# 2.net
KiCad netlist of a schematic drawn in Altium Designer
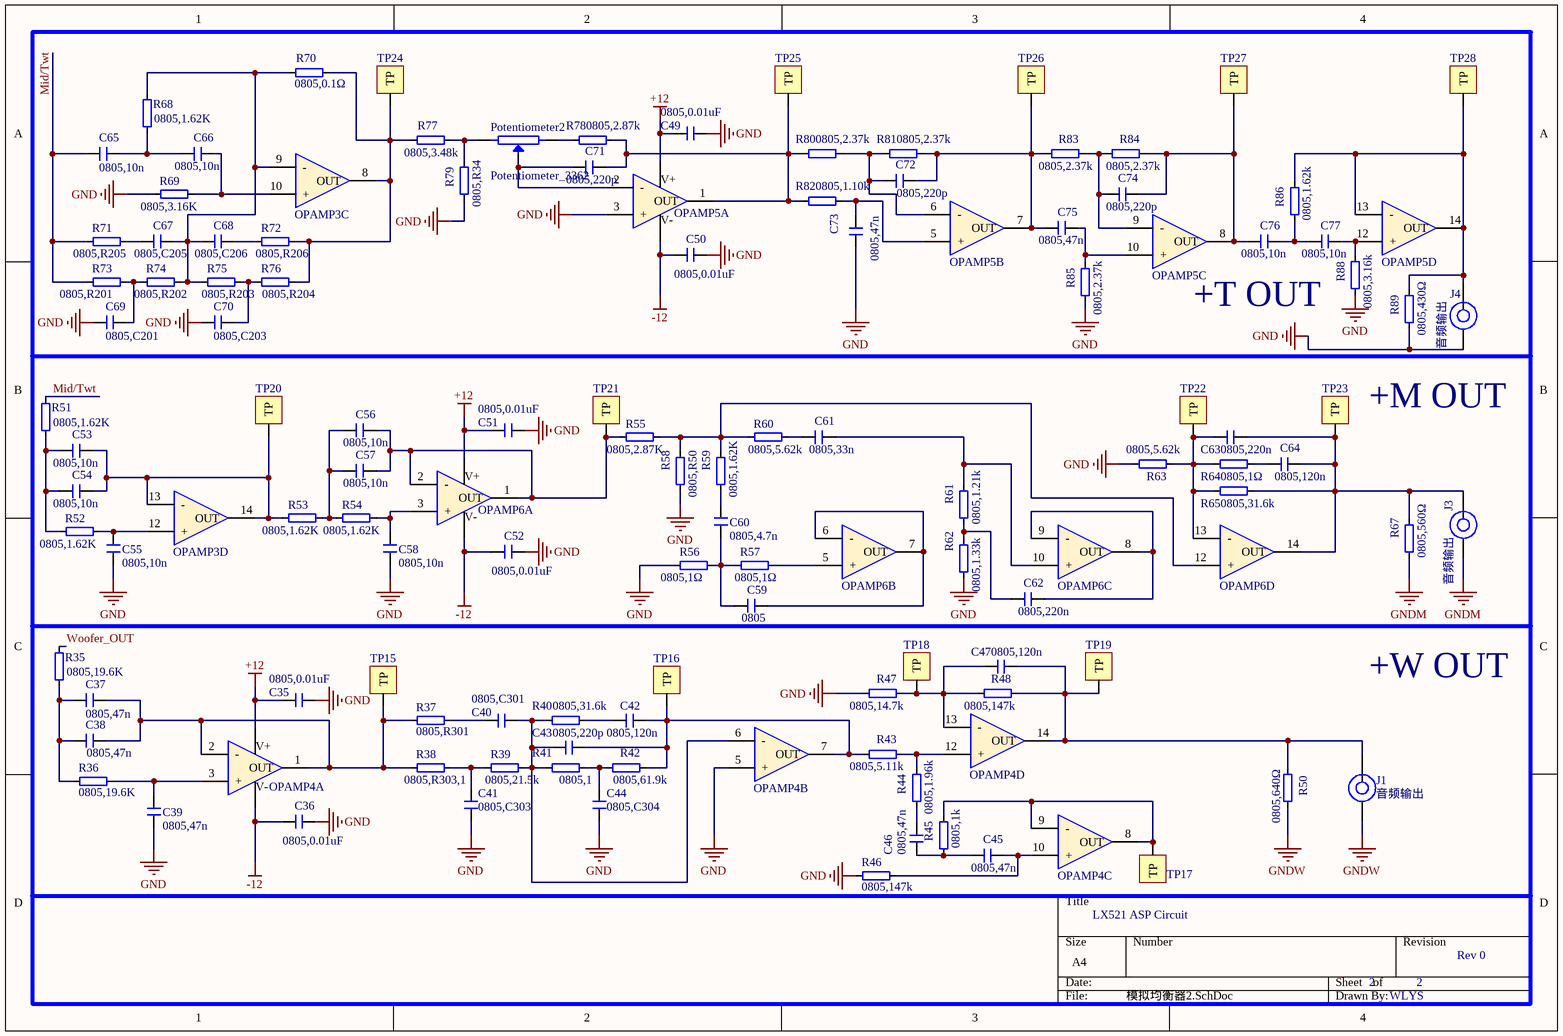
[diagram p0: 模拟均衡器2.SchDoc]

(export (version "E")
  (design (tool "Eeschema 10.0.6"))
  (components
    (comp (ref "C35")
      (value "0805,0.01uF")
      (footprint "0805_C")
      (description "0.01uF")
      (libsource (lib "模拟均衡器") (part "C0805"))
    )
    (comp (ref "C36")
      (value "0805,0.01uF")
      (footprint "0805_C")
      (description "0.01uF")
      (libsource (lib "模拟均衡器") (part "C0805"))
    )
    (comp (ref "C37") (value "0805,47n") (footprint "0805_C") (libsource (lib "模拟均衡器") (part "C0805")))
    (comp (ref "C38") (value "0805,47n") (footprint "0805_C") (libsource (lib "模拟均衡器") (part "C0805")))
    (comp (ref "C39") (value "0805,47n") (footprint "0805_C") (libsource (lib "模拟均衡器") (part "C0805")))
    (comp (ref "C40")
      (value "0805,C301")
      (footprint "0805_C")
      (description "0.01uF")
      (libsource (lib "模拟均衡器") (part "C0805"))
    )
    (comp (ref "C41")
      (value "0805,C303")
      (footprint "0805_C")
      (description "0.01uF")
      (libsource (lib "模拟均衡器") (part "C0805"))
    )
    (comp (ref "C42")
      (value "0805,120n")
      (footprint "0805_C")
      (description "0.01uF")
      (libsource (lib "模拟均衡器") (part "C0805"))
    )
    (comp (ref "C43")
      (value "0805,220p")
      (footprint "0805_C")
      (description "0.01uF")
      (libsource (lib "模拟均衡器") (part "C0805"))
    )
    (comp (ref "C44")
      (value "0805,C304")
      (footprint "0805_C")
      (description "0.01uF")
      (libsource (lib "模拟均衡器") (part "C0805"))
    )
    (comp (ref "C45") (value "0805,47n") (footprint "0805_C") (libsource (lib "模拟均衡器") (part "C0805")))
    (comp (ref "C46") (value "0805,47n") (footprint "0805_C") (libsource (lib "模拟均衡器") (part "C0805")))
    (comp (ref "C47")
      (value "0805,120n")
      (footprint "0805_C")
      (description "0.01uF")
      (libsource (lib "模拟均衡器") (part "C0805"))
    )
    (comp (ref "C49")
      (value "0805,0.01uF")
      (footprint "0805_C")
      (description "0.01uF")
      (libsource (lib "模拟均衡器") (part "C0805"))
    )
    (comp (ref "C50")
      (value "0805,0.01uF")
      (footprint "0805_C")
      (description "0.01uF")
      (libsource (lib "模拟均衡器") (part "C0805"))
    )
    (comp (ref "C51")
      (value "0805,0.01uF")
      (footprint "0805_C")
      (description "0.01uF")
      (libsource (lib "模拟均衡器") (part "C0805"))
    )
    (comp (ref "C52")
      (value "0805,0.01uF")
      (footprint "0805_C")
      (description "0.01uF")
      (libsource (lib "模拟均衡器") (part "C0805"))
    )
    (comp (ref "C53") (value "0805,10n") (footprint "0805_C") (libsource (lib "模拟均衡器") (part "C0805")))
    (comp (ref "C54") (value "0805,10n") (footprint "0805_C") (libsource (lib "模拟均衡器") (part "C0805")))
    (comp (ref "C55") (value "0805,10n") (footprint "0805_C") (libsource (lib "模拟均衡器") (part "C0805")))
    (comp (ref "C56") (value "0805,10n") (footprint "0805_C") (libsource (lib "模拟均衡器") (part "C0805")))
    (comp (ref "C57") (value "0805,10n") (footprint "0805_C") (libsource (lib "模拟均衡器") (part "C0805")))
    (comp (ref "C58") (value "0805,10n") (footprint "0805_C") (libsource (lib "模拟均衡器") (part "C0805")))
    (comp (ref "C59") (value "0805") (footprint "0805_C") (libsource (lib "模拟均衡器") (part "C0805")))
    (comp (ref "C60") (value "0805,4.7n") (footprint "0805_C") (libsource (lib "模拟均衡器") (part "C0805")))
    (comp (ref "C61") (value "0805,33n") (footprint "0805_C") (libsource (lib "模拟均衡器") (part "C0805")))
    (comp (ref "C62") (value "0805,220n") (footprint "0805_C") (libsource (lib "模拟均衡器") (part "C0805")))
    (comp (ref "C63") (value "0805,220n") (footprint "0805_C") (libsource (lib "模拟均衡器") (part "C0805")))
    (comp (ref "C64") (value "0805,120n") (footprint "0805_C") (libsource (lib "模拟均衡器") (part "C0805")))
    (comp (ref "C65") (value "0805,10n") (footprint "0805_C") (libsource (lib "模拟均衡器") (part "C0805")))
    (comp (ref "C66") (value "0805,10n") (footprint "0805_C") (libsource (lib "模拟均衡器") (part "C0805")))
    (comp (ref "C67") (value "0805,C205") (footprint "0805_C") (libsource (lib "模拟均衡器") (part "C0805")))
    (comp (ref "C68") (value "0805,C206") (footprint "0805_C") (libsource (lib "模拟均衡器") (part "C0805")))
    (comp (ref "C69") (value "0805,C201") (footprint "0805_C") (libsource (lib "模拟均衡器") (part "C0805")))
    (comp (ref "C70") (value "0805,C203") (footprint "0805_C") (libsource (lib "模拟均衡器") (part "C0805")))
    (comp (ref "C71") (value "0805,220p") (footprint "0805_C") (libsource (lib "模拟均衡器") (part "C0805")))
    (comp (ref "C72") (value "0805,220p") (footprint "0805_C") (libsource (lib "模拟均衡器") (part "C0805")))
    (comp (ref "C73") (value "0805,47n") (footprint "0805_C") (libsource (lib "模拟均衡器") (part "C0805")))
    (comp (ref "C74") (value "0805,220p") (footprint "0805_C") (libsource (lib "模拟均衡器") (part "C0805")))
    (comp (ref "C75") (value "0805,47n") (footprint "0805_C") (libsource (lib "模拟均衡器") (part "C0805")))
    (comp (ref "C76") (value "0805,10n") (footprint "0805_C") (libsource (lib "模拟均衡器") (part "C0805")))
    (comp (ref "C77") (value "0805,10n") (footprint "0805_C") (libsource (lib "模拟均衡器") (part "C0805")))
    (comp (ref "J1") (value "音频输出") (libsource (lib "模拟均衡器") (part "音频输出")))
    (comp (ref "J3") (value "音频输出") (libsource (lib "模拟均衡器") (part "音频输出")))
    (comp (ref "J4") (value "音频输出") (libsource (lib "模拟均衡器") (part "音频输出")))
    (comp (ref "OPAMP3")
      (value "4277UA")
      (footprint "SOIC-14_150mil")
      (libsource (lib "模拟均衡器") (part "OPA4277UA"))
    )
    (comp (ref "OPAMP4")
      (value "4277UA")
      (footprint "SOIC-14_150mil")
      (libsource (lib "模拟均衡器") (part "OPA4277UA"))
    )
    (comp (ref "OPAMP5")
      (value "4277UA")
      (footprint "SOIC-14_150mil")
      (libsource (lib "模拟均衡器") (part "OPA4277UA"))
    )
    (comp (ref "OPAMP6")
      (value "4277UA")
      (footprint "SOIC-14_150mil")
      (libsource (lib "模拟均衡器") (part "OPA4277UA"))
    )
    (comp (ref "Potentiometer2")
      (value "Potentiometer_3362")
      (footprint "3362P")
      (libsource (lib "模拟均衡器") (part "Potentiometer_3362"))
    )
    (comp (ref "R35") (value "0805,19.6K") (footprint "0805_R") (libsource (lib "模拟均衡器") (part "R0805")))
    (comp (ref "R36") (value "0805,19.6K") (footprint "0805_R") (libsource (lib "模拟均衡器") (part "R0805")))
    (comp (ref "R37") (value "0805,R301") (footprint "0805_R") (libsource (lib "模拟均衡器") (part "R0805")))
    (comp (ref "R38") (value "0805,R303,1") (footprint "0805_R") (libsource (lib "模拟均衡器") (part "R0805")))
    (comp (ref "R39") (value "0805,21.5k") (footprint "0805_R") (libsource (lib "模拟均衡器") (part "R0805")))
    (comp (ref "R40") (value "0805,31.6k") (footprint "0805_R") (libsource (lib "模拟均衡器") (part "R0805")))
    (comp (ref "R41") (value "0805,1") (footprint "0805_R") (libsource (lib "模拟均衡器") (part "R0805")))
    (comp (ref "R42") (value "0805,61.9k") (footprint "0805_R") (libsource (lib "模拟均衡器") (part "R0805")))
    (comp (ref "R43") (value "0805,5.11k") (footprint "0805_R") (libsource (lib "模拟均衡器") (part "R0805")))
    (comp (ref "R44") (value "0805,1.96k") (footprint "0805_R") (libsource (lib "模拟均衡器") (part "R0805")))
    (comp (ref "R45") (value "0805,1k") (footprint "0805_R") (libsource (lib "模拟均衡器") (part "R0805")))
    (comp (ref "R46") (value "0805,147k") (footprint "0805_R") (libsource (lib "模拟均衡器") (part "R0805")))
    (comp (ref "R47") (value "0805,14.7k") (footprint "0805_R") (libsource (lib "模拟均衡器") (part "R0805")))
    (comp (ref "R48") (value "0805,147k") (footprint "0805_R") (libsource (lib "模拟均衡器") (part "R0805")))
    (comp (ref "R50") (value "0805,640Ω") (footprint "0805_R") (libsource (lib "模拟均衡器") (part "R0805")))
    (comp (ref "R51") (value "0805,1.62K") (footprint "0805_R") (libsource (lib "模拟均衡器") (part "R0805")))
    (comp (ref "R52") (value "0805,1.62K") (footprint "0805_R") (libsource (lib "模拟均衡器") (part "R0805")))
    (comp (ref "R53") (value "0805,1.62K") (footprint "0805_R") (libsource (lib "模拟均衡器") (part "R0805")))
    (comp (ref "R54") (value "0805,1.62K") (footprint "0805_R") (libsource (lib "模拟均衡器") (part "R0805")))
    (comp (ref "R55") (value "0805,2.87K") (footprint "0805_R") (libsource (lib "模拟均衡器") (part "R0805")))
    (comp (ref "R56") (value "0805,1Ω") (footprint "0805_R") (libsource (lib "模拟均衡器") (part "R0805")))
    (comp (ref "R57") (value "0805,1Ω") (footprint "0805_R") (libsource (lib "模拟均衡器") (part "R0805")))
    (comp (ref "R58") (value "0805,R50") (footprint "0805_R") (libsource (lib "模拟均衡器") (part "R0805")))
    (comp (ref "R59") (value "0805,1.62K") (footprint "0805_R") (libsource (lib "模拟均衡器") (part "R0805")))
    (comp (ref "R60") (value "0805,5.62k") (footprint "0805_R") (libsource (lib "模拟均衡器") (part "R0805")))
    (comp (ref "R61") (value "0805,1.21k") (footprint "0805_R") (libsource (lib "模拟均衡器") (part "R0805")))
    (comp (ref "R62") (value "0805,1.33k") (footprint "0805_R") (libsource (lib "模拟均衡器") (part "R0805")))
    (comp (ref "R63") (value "0805,5.62k") (footprint "0805_R") (libsource (lib "模拟均衡器") (part "R0805")))
    (comp (ref "R64") (value "0805,1Ω") (footprint "0805_R") (libsource (lib "模拟均衡器") (part "R0805")))
    (comp (ref "R65") (value "0805,31.6k") (footprint "0805_R") (libsource (lib "模拟均衡器") (part "R0805")))
    (comp (ref "R67") (value "0805,560Ω") (footprint "0805_R") (libsource (lib "模拟均衡器") (part "R0805")))
    (comp (ref "R68") (value "0805,1.62K") (footprint "0805_R") (libsource (lib "模拟均衡器") (part "R0805")))
    (comp (ref "R69") (value "0805,3.16K") (footprint "0805_R") (libsource (lib "模拟均衡器") (part "R0805")))
    (comp (ref "R70") (value "0805,0.1Ω") (footprint "0805_R") (libsource (lib "模拟均衡器") (part "R0805")))
    (comp (ref "R71") (value "0805,R205") (footprint "0805_R") (libsource (lib "模拟均衡器") (part "R0805")))
    (comp (ref "R72") (value "0805,R206") (footprint "0805_R") (libsource (lib "模拟均衡器") (part "R0805")))
    (comp (ref "R73") (value "0805,R201") (footprint "0805_R") (libsource (lib "模拟均衡器") (part "R0805")))
    (comp (ref "R74") (value "0805,R202") (footprint "0805_R") (libsource (lib "模拟均衡器") (part "R0805")))
    (comp (ref "R75") (value "0805,R203") (footprint "0805_R") (libsource (lib "模拟均衡器") (part "R0805")))
    (comp (ref "R76") (value "0805,R204") (footprint "0805_R") (libsource (lib "模拟均衡器") (part "R0805")))
    (comp (ref "R77") (value "0805,3.48k") (footprint "0805_R") (libsource (lib "模拟均衡器") (part "R0805")))
    (comp (ref "R78") (value "0805,2.87k") (footprint "0805_R") (libsource (lib "模拟均衡器") (part "R0805")))
    (comp (ref "R79") (value "0805,R34") (footprint "0805_R") (libsource (lib "模拟均衡器") (part "R0805")))
    (comp (ref "R80") (value "0805,2.37k") (footprint "0805_R") (libsource (lib "模拟均衡器") (part "R0805")))
    (comp (ref "R81") (value "0805,2.37k") (footprint "0805_R") (libsource (lib "模拟均衡器") (part "R0805")))
    (comp (ref "R82") (value "0805,1.10k") (footprint "0805_R") (libsource (lib "模拟均衡器") (part "R0805")))
    (comp (ref "R83") (value "0805,2.37k") (footprint "0805_R") (libsource (lib "模拟均衡器") (part "R0805")))
    (comp (ref "R84") (value "0805,2.37k") (footprint "0805_R") (libsource (lib "模拟均衡器") (part "R0805")))
    (comp (ref "R85") (value "0805,2.37k") (footprint "0805_R") (libsource (lib "模拟均衡器") (part "R0805")))
    (comp (ref "R86") (value "0805,1.62k") (footprint "0805_R") (libsource (lib "模拟均衡器") (part "R0805")))
    (comp (ref "R88") (value "0805,3.16k") (footprint "0805_R") (libsource (lib "模拟均衡器") (part "R0805")))
    (comp (ref "R89") (value "0805,430Ω") (footprint "0805_R") (libsource (lib "模拟均衡器") (part "R0805")))
    (comp (ref "TP15") (value "测试点") (footprint "TestPoint") (libsource (lib "模拟均衡器") (part "测试点")))
    (comp (ref "TP16") (value "测试点") (footprint "TestPoint") (libsource (lib "模拟均衡器") (part "测试点")))
    (comp (ref "TP17") (value "测试点") (footprint "TestPoint") (libsource (lib "") (part "测试点_1")))
    (comp (ref "TP18") (value "测试点") (footprint "TestPoint") (libsource (lib "模拟均衡器") (part "测试点")))
    (comp (ref "TP19") (value "测试点") (footprint "TestPoint") (libsource (lib "模拟均衡器") (part "测试点")))
    (comp (ref "TP20") (value "测试点") (footprint "TestPoint") (libsource (lib "模拟均衡器") (part "测试点")))
    (comp (ref "TP21") (value "测试点") (footprint "TestPoint") (libsource (lib "模拟均衡器") (part "测试点")))
    (comp (ref "TP22") (value "测试点") (footprint "TestPoint") (libsource (lib "模拟均衡器") (part "测试点")))
    (comp (ref "TP23") (value "测试点") (footprint "TestPoint") (libsource (lib "模拟均衡器") (part "测试点")))
    (comp (ref "TP24") (value "测试点") (footprint "TestPoint") (libsource (lib "模拟均衡器") (part "测试点")))
    (comp (ref "TP25") (value "测试点") (footprint "TestPoint") (libsource (lib "模拟均衡器") (part "测试点")))
    (comp (ref "TP26") (value "测试点") (footprint "TestPoint") (libsource (lib "模拟均衡器") (part "测试点")))
    (comp (ref "TP27") (value "测试点") (footprint "TestPoint") (libsource (lib "模拟均衡器") (part "测试点")))
    (comp (ref "TP28") (value "测试点") (footprint "TestPoint") (libsource (lib "模拟均衡器") (part "测试点")))
  )
  (nets
    (net (code "1") (name "+12") (class "Default")
      (node (ref "C35") (pin "1") (pinfunction "1_1") (pintype "passive"))
      (node (ref "C49") (pin "1") (pinfunction "1_1") (pintype "passive"))
      (node (ref "C51") (pin "1") (pinfunction "1_1") (pintype "passive"))
      (node (ref "OPAMP4") (pin "4") (pinfunction "V+_4") (pintype "passive"))
      (node (ref "OPAMP5") (pin "4") (pinfunction "V+_4") (pintype "passive"))
      (node (ref "OPAMP6") (pin "4") (pinfunction "V+_4") (pintype "passive"))
    )
    (net (code "2") (name "-12") (class "Default")
      (node (ref "C36") (pin "1") (pinfunction "1_1") (pintype "passive"))
      (node (ref "C50") (pin "1") (pinfunction "1_1") (pintype "passive"))
      (node (ref "C52") (pin "1") (pinfunction "1_1") (pintype "passive"))
      (node (ref "OPAMP4") (pin "11") (pinfunction "V-_11") (pintype "passive"))
      (node (ref "OPAMP5") (pin "11") (pinfunction "V-_11") (pintype "passive"))
      (node (ref "OPAMP6") (pin "11") (pinfunction "V-_11") (pintype "passive"))
    )
    (net (code "3") (name "/Mid{slash}Twt") (class "Default")
      (node (ref "C65") (pin "1") (pinfunction "1_1") (pintype "passive"))
      (node (ref "R51") (pin "1") (pinfunction "1_1") (pintype "passive"))
      (node (ref "R71") (pin "1") (pinfunction "1_1") (pintype "passive"))
      (node (ref "R73") (pin "1") (pinfunction "1_1") (pintype "passive"))
    )
    (net (code "4") (name "/Woofer_OUT") (class "Default")
      (node (ref "R35") (pin "1") (pinfunction "1_1") (pintype "passive"))
    )
    (net (code "5") (name "GND") (class "Default")
      (node (ref "C35") (pin "2") (pinfunction "2_2") (pintype "passive"))
      (node (ref "C36") (pin "2") (pinfunction "2_2") (pintype "passive"))
      (node (ref "C39") (pin "2") (pinfunction "2_2") (pintype "passive"))
      (node (ref "C41") (pin "1") (pinfunction "1_1") (pintype "passive"))
      (node (ref "C44") (pin "1") (pinfunction "1_1") (pintype "passive"))
      (node (ref "C49") (pin "2") (pinfunction "2_2") (pintype "passive"))
      (node (ref "C50") (pin "2") (pinfunction "2_2") (pintype "passive"))
      (node (ref "C51") (pin "2") (pinfunction "2_2") (pintype "passive"))
      (node (ref "C52") (pin "2") (pinfunction "2_2") (pintype "passive"))
      (node (ref "C55") (pin "2") (pinfunction "2_2") (pintype "passive"))
      (node (ref "C58") (pin "2") (pinfunction "2_2") (pintype "passive"))
      (node (ref "C69") (pin "2") (pinfunction "2_2") (pintype "passive"))
      (node (ref "C70") (pin "1") (pinfunction "1_1") (pintype "passive"))
      (node (ref "C73") (pin "2") (pinfunction "2_2") (pintype "passive"))
      (node (ref "J4") (pin "2") (pinfunction "GND_2") (pintype "passive"))
      (node (ref "OPAMP4") (pin "5") (pinfunction "+_5") (pintype "passive"))
      (node (ref "OPAMP5") (pin "3") (pinfunction "+_3") (pintype "passive"))
      (node (ref "R46") (pin "2") (pinfunction "2_2") (pintype "passive"))
      (node (ref "R47") (pin "1") (pinfunction "1_1") (pintype "passive"))
      (node (ref "R56") (pin "1") (pinfunction "1_1") (pintype "passive"))
      (node (ref "R58") (pin "1") (pinfunction "1_1") (pintype "passive"))
      (node (ref "R62") (pin "1") (pinfunction "1_1") (pintype "passive"))
      (node (ref "R63") (pin "1") (pinfunction "1_1") (pintype "passive"))
      (node (ref "R69") (pin "1") (pinfunction "1_1") (pintype "passive"))
      (node (ref "R79") (pin "1") (pinfunction "1_1") (pintype "passive"))
      (node (ref "R85") (pin "1") (pinfunction "1_1") (pintype "passive"))
      (node (ref "R88") (pin "2") (pinfunction "2_2") (pintype "passive"))
      (node (ref "R89") (pin "2") (pinfunction "2_2") (pintype "passive"))
    )
    (net (code "6") (name "GNDM") (class "Default")
      (node (ref "J3") (pin "2") (pinfunction "GND_2") (pintype "passive"))
      (node (ref "R67") (pin "1") (pinfunction "1_1") (pintype "passive"))
    )
    (net (code "7") (name "GNDW") (class "Default")
      (node (ref "J1") (pin "2") (pinfunction "GND_2") (pintype "passive"))
      (node (ref "R50") (pin "2") (pinfunction "2_2") (pintype "passive"))
    )
    (net (code "8") (name "Net-(C37-Pad2)") (class "Default")
      (node (ref "C37") (pin "2") (pinfunction "2_2") (pintype "passive"))
      (node (ref "C38") (pin "2") (pinfunction "2_2") (pintype "passive"))
      (node (ref "R35") (pin "2") (pinfunction "2_2") (pintype "passive"))
      (node (ref "R36") (pin "1") (pinfunction "1_1") (pintype "passive"))
    )
    (net (code "9") (name "Net-(C40-Pad1)") (class "Default")
      (node (ref "C40") (pin "1") (pinfunction "1_1") (pintype "passive"))
      (node (ref "R37") (pin "2") (pinfunction "2_2") (pintype "passive"))
    )
    (net (code "10") (name "Net-(C41-Pad2)") (class "Default")
      (node (ref "C41") (pin "2") (pinfunction "2_2") (pintype "passive"))
      (node (ref "R38") (pin "2") (pinfunction "2_2") (pintype "passive"))
      (node (ref "R39") (pin "1") (pinfunction "1_1") (pintype "passive"))
    )
    (net (code "11") (name "Net-(C42-Pad1)") (class "Default")
      (node (ref "C42") (pin "1") (pinfunction "1_1") (pintype "passive"))
      (node (ref "R40") (pin "2") (pinfunction "2_2") (pintype "passive"))
    )
    (net (code "12") (name "Net-(C44-Pad2)") (class "Default")
      (node (ref "C44") (pin "2") (pinfunction "2_2") (pintype "passive"))
      (node (ref "R41") (pin "2") (pinfunction "2_2") (pintype "passive"))
      (node (ref "R42") (pin "1") (pinfunction "1_1") (pintype "passive"))
    )
    (net (code "13") (name "Net-(C45-Pad1)") (class "Default")
      (node (ref "C45") (pin "1") (pinfunction "1_1") (pintype "passive"))
      (node (ref "C46") (pin "2") (pinfunction "2_2") (pintype "passive"))
      (node (ref "R45") (pin "1") (pinfunction "1_1") (pintype "passive"))
    )
    (net (code "14") (name "Net-(C46-Pad1)") (class "Default")
      (node (ref "C46") (pin "1") (pinfunction "1_1") (pintype "passive"))
      (node (ref "R44") (pin "1") (pinfunction "1_1") (pintype "passive"))
    )
    (net (code "15") (name "Net-(C53-Pad2)") (class "Default")
      (node (ref "C53") (pin "2") (pinfunction "2_2") (pintype "passive"))
      (node (ref "C54") (pin "2") (pinfunction "2_2") (pintype "passive"))
      (node (ref "R51") (pin "2") (pinfunction "2_2") (pintype "passive"))
      (node (ref "R52") (pin "1") (pinfunction "1_1") (pintype "passive"))
    )
    (net (code "16") (name "Net-(C56-Pad1)") (class "Default")
      (node (ref "C56") (pin "1") (pinfunction "1_1") (pintype "passive"))
      (node (ref "C57") (pin "1") (pinfunction "1_1") (pintype "passive"))
      (node (ref "R53") (pin "2") (pinfunction "2_2") (pintype "passive"))
      (node (ref "R54") (pin "1") (pinfunction "1_1") (pintype "passive"))
    )
    (net (code "17") (name "Net-(C59-Pad1)") (class "Default")
      (node (ref "C59") (pin "1") (pinfunction "1_1") (pintype "passive"))
      (node (ref "C60") (pin "1") (pinfunction "1_1") (pintype "passive"))
      (node (ref "R56") (pin "2") (pinfunction "2_2") (pintype "passive"))
      (node (ref "R57") (pin "1") (pinfunction "1_1") (pintype "passive"))
    )
    (net (code "18") (name "Net-(C60-Pad2)") (class "Default")
      (node (ref "C60") (pin "2") (pinfunction "2_2") (pintype "passive"))
      (node (ref "R59") (pin "1") (pinfunction "1_1") (pintype "passive"))
    )
    (net (code "19") (name "Net-(C61-Pad1)") (class "Default")
      (node (ref "C61") (pin "1") (pinfunction "1_1") (pintype "passive"))
      (node (ref "R60") (pin "2") (pinfunction "2_2") (pintype "passive"))
    )
    (net (code "20") (name "Net-(C62-Pad1)") (class "Default")
      (node (ref "C62") (pin "1") (pinfunction "1_1") (pintype "passive"))
      (node (ref "R61") (pin "1") (pinfunction "1_1") (pintype "passive"))
      (node (ref "R62") (pin "2") (pinfunction "2_2") (pintype "passive"))
    )
    (net (code "21") (name "Net-(C64-Pad1)") (class "Default")
      (node (ref "C64") (pin "1") (pinfunction "1_1") (pintype "passive"))
      (node (ref "R64") (pin "2") (pinfunction "2_2") (pintype "passive"))
    )
    (net (code "22") (name "Net-(C65-Pad2)") (class "Default")
      (node (ref "C65") (pin "2") (pinfunction "2_2") (pintype "passive"))
      (node (ref "C66") (pin "2") (pinfunction "2_2") (pintype "passive"))
      (node (ref "R68") (pin "2") (pinfunction "2_2") (pintype "passive"))
    )
    (net (code "23") (name "Net-(C67-Pad2)") (class "Default")
      (node (ref "C67") (pin "2") (pinfunction "2_2") (pintype "passive"))
      (node (ref "R71") (pin "2") (pinfunction "2_2") (pintype "passive"))
    )
    (net (code "24") (name "Net-(C68-Pad1)") (class "Default")
      (node (ref "C68") (pin "1") (pinfunction "1_1") (pintype "passive"))
      (node (ref "R72") (pin "1") (pinfunction "1_1") (pintype "passive"))
    )
    (net (code "25") (name "Net-(C69-Pad1)") (class "Default")
      (node (ref "C69") (pin "1") (pinfunction "1_1") (pintype "passive"))
      (node (ref "R73") (pin "2") (pinfunction "2_2") (pintype "passive"))
      (node (ref "R74") (pin "1") (pinfunction "1_1") (pintype "passive"))
    )
    (net (code "26") (name "Net-(C70-Pad2)") (class "Default")
      (node (ref "C70") (pin "2") (pinfunction "2_2") (pintype "passive"))
      (node (ref "R75") (pin "2") (pinfunction "2_2") (pintype "passive"))
      (node (ref "R76") (pin "1") (pinfunction "1_1") (pintype "passive"))
    )
    (net (code "27") (name "Net-(C76-Pad2)") (class "Default")
      (node (ref "C76") (pin "2") (pinfunction "2_2") (pintype "passive"))
      (node (ref "C77") (pin "1") (pinfunction "1_1") (pintype "passive"))
      (node (ref "R86") (pin "1") (pinfunction "1_1") (pintype "passive"))
    )
    (net (code "28") (name "Net-(J1-MIC)") (class "Default")
      (node (ref "C47") (pin "2") (pinfunction "2_2") (pintype "passive"))
      (node (ref "J1") (pin "1") (pinfunction "MIC_1") (pintype "passive"))
      (node (ref "OPAMP4") (pin "14") (pinfunction "OUT_14") (pintype "passive"))
      (node (ref "R48") (pin "2") (pinfunction "2_2") (pintype "passive"))
      (node (ref "R50") (pin "1") (pinfunction "1_1") (pintype "passive"))
      (node (ref "TP19") (pin "1") (pinfunction "TP_1") (pintype "passive"))
    )
    (net (code "29") (name "Net-(J3-MIC)") (class "Default")
      (node (ref "C63") (pin "2") (pinfunction "2_2") (pintype "passive"))
      (node (ref "C64") (pin "2") (pinfunction "2_2") (pintype "passive"))
      (node (ref "J3") (pin "1") (pinfunction "MIC_1") (pintype "passive"))
      (node (ref "OPAMP6") (pin "14") (pinfunction "OUT_14") (pintype "passive"))
      (node (ref "R65") (pin "2") (pinfunction "2_2") (pintype "passive"))
      (node (ref "R67") (pin "2") (pinfunction "2_2") (pintype "passive"))
      (node (ref "TP23") (pin "1") (pinfunction "TP_1") (pintype "passive"))
    )
    (net (code "30") (name "Net-(J4-MIC)") (class "Default")
      (node (ref "J4") (pin "1") (pinfunction "MIC_1") (pintype "passive"))
      (node (ref "OPAMP5") (pin "13") (pinfunction "-_13") (pintype "passive"))
      (node (ref "OPAMP5") (pin "14") (pinfunction "OUT_14") (pintype "passive"))
      (node (ref "R86") (pin "2") (pinfunction "2_2") (pintype "passive"))
      (node (ref "R89") (pin "1") (pinfunction "1_1") (pintype "passive"))
      (node (ref "TP28") (pin "1") (pinfunction "TP_1") (pintype "passive"))
    )
    (net (code "31") (name "Net-(OPAMP3C-+)") (class "Default")
      (node (ref "C66") (pin "1") (pinfunction "1_1") (pintype "passive"))
      (node (ref "OPAMP3") (pin "10") (pinfunction "+_10") (pintype "passive"))
      (node (ref "R69") (pin "2") (pinfunction "2_2") (pintype "passive"))
    )
    (net (code "32") (name "Net-(OPAMP3C--)") (class "Default")
      (node (ref "C67") (pin "1") (pinfunction "1_1") (pintype "passive"))
      (node (ref "C68") (pin "2") (pinfunction "2_2") (pintype "passive"))
      (node (ref "OPAMP3") (pin "9") (pinfunction "-_9") (pintype "passive"))
      (node (ref "R68") (pin "1") (pinfunction "1_1") (pintype "passive"))
      (node (ref "R70") (pin "1") (pinfunction "1_1") (pintype "passive"))
      (node (ref "R74") (pin "2") (pinfunction "2_2") (pintype "passive"))
      (node (ref "R75") (pin "1") (pinfunction "1_1") (pintype "passive"))
    )
    (net (code "33") (name "Net-(OPAMP3C-OUT)") (class "Default")
      (node (ref "OPAMP3") (pin "8") (pinfunction "OUT_8") (pintype "passive"))
      (node (ref "R70") (pin "2") (pinfunction "2_2") (pintype "passive"))
      (node (ref "R72") (pin "2") (pinfunction "2_2") (pintype "passive"))
      (node (ref "R76") (pin "2") (pinfunction "2_2") (pintype "passive"))
      (node (ref "R77") (pin "1") (pinfunction "1_1") (pintype "passive"))
      (node (ref "TP24") (pin "1") (pinfunction "TP_1") (pintype "passive"))
    )
    (net (code "34") (name "Net-(OPAMP3D-+)") (class "Default")
      (node (ref "C55") (pin "1") (pinfunction "1_1") (pintype "passive"))
      (node (ref "OPAMP3") (pin "12") (pinfunction "+_12") (pintype "passive"))
      (node (ref "R52") (pin "2") (pinfunction "2_2") (pintype "passive"))
    )
    (net (code "35") (name "Net-(OPAMP3D--)") (class "Default")
      (node (ref "C53") (pin "1") (pinfunction "1_1") (pintype "passive"))
      (node (ref "C54") (pin "1") (pinfunction "1_1") (pintype "passive"))
      (node (ref "OPAMP3") (pin "13") (pinfunction "-_13") (pintype "passive"))
      (node (ref "OPAMP3") (pin "14") (pinfunction "OUT_14") (pintype "passive"))
      (node (ref "R53") (pin "1") (pinfunction "1_1") (pintype "passive"))
      (node (ref "TP20") (pin "1") (pinfunction "TP_1") (pintype "passive"))
    )
    (net (code "36") (name "Net-(OPAMP4A-+)") (class "Default")
      (node (ref "C39") (pin "1") (pinfunction "1_1") (pintype "passive"))
      (node (ref "OPAMP4") (pin "3") (pinfunction "+_3") (pintype "passive"))
      (node (ref "R36") (pin "2") (pinfunction "2_2") (pintype "passive"))
    )
    (net (code "37") (name "Net-(OPAMP4A--)") (class "Default")
      (node (ref "C37") (pin "1") (pinfunction "1_1") (pintype "passive"))
      (node (ref "C38") (pin "1") (pinfunction "1_1") (pintype "passive"))
      (node (ref "OPAMP4") (pin "1") (pinfunction "OUT_1") (pintype "passive"))
      (node (ref "OPAMP4") (pin "2") (pinfunction "-_2") (pintype "passive"))
      (node (ref "R37") (pin "1") (pinfunction "1_1") (pintype "passive"))
      (node (ref "R38") (pin "1") (pinfunction "1_1") (pintype "passive"))
      (node (ref "TP15") (pin "1") (pinfunction "TP_1") (pintype "passive"))
    )
    (net (code "38") (name "Net-(OPAMP4B--)") (class "Default")
      (node (ref "C40") (pin "2") (pinfunction "2_2") (pintype "passive"))
      (node (ref "C43") (pin "1") (pinfunction "1_1") (pintype "passive"))
      (node (ref "OPAMP4") (pin "6") (pinfunction "-_6") (pintype "passive"))
      (node (ref "R39") (pin "2") (pinfunction "2_2") (pintype "passive"))
      (node (ref "R40") (pin "1") (pinfunction "1_1") (pintype "passive"))
      (node (ref "R41") (pin "1") (pinfunction "1_1") (pintype "passive"))
    )
    (net (code "39") (name "Net-(OPAMP4B-OUT)") (class "Default")
      (node (ref "C42") (pin "2") (pinfunction "2_2") (pintype "passive"))
      (node (ref "C43") (pin "2") (pinfunction "2_2") (pintype "passive"))
      (node (ref "OPAMP4") (pin "7") (pinfunction "OUT_7") (pintype "passive"))
      (node (ref "R42") (pin "2") (pinfunction "2_2") (pintype "passive"))
      (node (ref "R43") (pin "1") (pinfunction "1_1") (pintype "passive"))
      (node (ref "TP16") (pin "1") (pinfunction "TP_1") (pintype "passive"))
    )
    (net (code "40") (name "Net-(OPAMP4C-+)") (class "Default")
      (node (ref "C45") (pin "2") (pinfunction "2_2") (pintype "passive"))
      (node (ref "OPAMP4") (pin "10") (pinfunction "+_10") (pintype "passive"))
      (node (ref "R46") (pin "1") (pinfunction "1_1") (pintype "passive"))
    )
    (net (code "41") (name "Net-(OPAMP4C--)") (class "Default")
      (node (ref "OPAMP4") (pin "8") (pinfunction "OUT_8") (pintype "passive"))
      (node (ref "OPAMP4") (pin "9") (pinfunction "-_9") (pintype "passive"))
      (node (ref "R45") (pin "2") (pinfunction "2_2") (pintype "passive"))
      (node (ref "TP17") (pin "1") (pinfunction "TP_1") (pintype "passive"))
    )
    (net (code "42") (name "Net-(OPAMP4D-+)") (class "Default")
      (node (ref "OPAMP4") (pin "12") (pinfunction "+_12") (pintype "passive"))
      (node (ref "R43") (pin "2") (pinfunction "2_2") (pintype "passive"))
      (node (ref "R44") (pin "2") (pinfunction "2_2") (pintype "passive"))
    )
    (net (code "43") (name "Net-(OPAMP4D--)") (class "Default")
      (node (ref "C47") (pin "1") (pinfunction "1_1") (pintype "passive"))
      (node (ref "OPAMP4") (pin "13") (pinfunction "-_13") (pintype "passive"))
      (node (ref "R47") (pin "2") (pinfunction "2_2") (pintype "passive"))
      (node (ref "R48") (pin "1") (pinfunction "1_1") (pintype "passive"))
      (node (ref "TP18") (pin "1") (pinfunction "TP_1") (pintype "passive"))
    )
    (net (code "44") (name "Net-(OPAMP5A--)") (class "Default")
      (node (ref "C71") (pin "2") (pinfunction "2_2") (pintype "passive"))
      (node (ref "OPAMP5") (pin "2") (pinfunction "-_2") (pintype "passive"))
      (node (ref "Potentiometer2") (pin "2") (pinfunction "W_2") (pintype "passive"))
    )
    (net (code "45") (name "Net-(OPAMP5A-OUT)") (class "Default")
      (node (ref "C71") (pin "1") (pinfunction "1_1") (pintype "passive"))
      (node (ref "OPAMP5") (pin "1") (pinfunction "OUT_1") (pintype "passive"))
      (node (ref "R78") (pin "2") (pinfunction "2_2") (pintype "passive"))
      (node (ref "R80") (pin "1") (pinfunction "1_1") (pintype "passive"))
      (node (ref "R82") (pin "1") (pinfunction "1_1") (pintype "passive"))
      (node (ref "TP25") (pin "1") (pinfunction "TP_1") (pintype "passive"))
    )
    (net (code "46") (name "Net-(OPAMP5B-+)") (class "Default")
      (node (ref "C73") (pin "1") (pinfunction "1_1") (pintype "passive"))
      (node (ref "OPAMP5") (pin "5") (pinfunction "+_5") (pintype "passive"))
      (node (ref "R82") (pin "2") (pinfunction "2_2") (pintype "passive"))
    )
    (net (code "47") (name "Net-(OPAMP5B--)") (class "Default")
      (node (ref "C72") (pin "1") (pinfunction "1_1") (pintype "passive"))
      (node (ref "OPAMP5") (pin "6") (pinfunction "-_6") (pintype "passive"))
      (node (ref "R80") (pin "2") (pinfunction "2_2") (pintype "passive"))
      (node (ref "R81") (pin "1") (pinfunction "1_1") (pintype "passive"))
    )
    (net (code "48") (name "Net-(OPAMP5B-OUT)") (class "Default")
      (node (ref "C72") (pin "2") (pinfunction "2_2") (pintype "passive"))
      (node (ref "C75") (pin "1") (pinfunction "1_1") (pintype "passive"))
      (node (ref "OPAMP5") (pin "7") (pinfunction "OUT_7") (pintype "passive"))
      (node (ref "R81") (pin "2") (pinfunction "2_2") (pintype "passive"))
      (node (ref "R83") (pin "1") (pinfunction "1_1") (pintype "passive"))
      (node (ref "TP26") (pin "1") (pinfunction "TP_1") (pintype "passive"))
    )
    (net (code "49") (name "Net-(OPAMP5C-+)") (class "Default")
      (node (ref "C75") (pin "2") (pinfunction "2_2") (pintype "passive"))
      (node (ref "OPAMP5") (pin "10") (pinfunction "+_10") (pintype "passive"))
      (node (ref "R85") (pin "2") (pinfunction "2_2") (pintype "passive"))
    )
    (net (code "50") (name "Net-(OPAMP5C--)") (class "Default")
      (node (ref "C74") (pin "1") (pinfunction "1_1") (pintype "passive"))
      (node (ref "OPAMP5") (pin "9") (pinfunction "-_9") (pintype "passive"))
      (node (ref "R83") (pin "2") (pinfunction "2_2") (pintype "passive"))
      (node (ref "R84") (pin "1") (pinfunction "1_1") (pintype "passive"))
    )
    (net (code "51") (name "Net-(OPAMP5C-OUT)") (class "Default")
      (node (ref "C74") (pin "2") (pinfunction "2_2") (pintype "passive"))
      (node (ref "C76") (pin "1") (pinfunction "1_1") (pintype "passive"))
      (node (ref "OPAMP5") (pin "8") (pinfunction "OUT_8") (pintype "passive"))
      (node (ref "R84") (pin "2") (pinfunction "2_2") (pintype "passive"))
      (node (ref "TP27") (pin "1") (pinfunction "TP_1") (pintype "passive"))
    )
    (net (code "52") (name "Net-(OPAMP5D-+)") (class "Default")
      (node (ref "C77") (pin "2") (pinfunction "2_2") (pintype "passive"))
      (node (ref "OPAMP5") (pin "12") (pinfunction "+_12") (pintype "passive"))
      (node (ref "R88") (pin "1") (pinfunction "1_1") (pintype "passive"))
    )
    (net (code "53") (name "Net-(OPAMP6A-+)") (class "Default")
      (node (ref "C58") (pin "1") (pinfunction "1_1") (pintype "passive"))
      (node (ref "OPAMP6") (pin "3") (pinfunction "+_3") (pintype "passive"))
      (node (ref "R54") (pin "2") (pinfunction "2_2") (pintype "passive"))
    )
    (net (code "54") (name "Net-(OPAMP6A--)") (class "Default")
      (node (ref "C56") (pin "2") (pinfunction "2_2") (pintype "passive"))
      (node (ref "C57") (pin "2") (pinfunction "2_2") (pintype "passive"))
      (node (ref "OPAMP6") (pin "1") (pinfunction "OUT_1") (pintype "passive"))
      (node (ref "OPAMP6") (pin "2") (pinfunction "-_2") (pintype "passive"))
      (node (ref "R55") (pin "1") (pinfunction "1_1") (pintype "passive"))
      (node (ref "TP21") (pin "1") (pinfunction "TP_1") (pintype "passive"))
    )
    (net (code "55") (name "Net-(OPAMP6B-+)") (class "Default")
      (node (ref "OPAMP6") (pin "5") (pinfunction "+_5") (pintype "passive"))
      (node (ref "R57") (pin "2") (pinfunction "2_2") (pintype "passive"))
    )
    (net (code "56") (name "Net-(OPAMP6B--)") (class "Default")
      (node (ref "C59") (pin "2") (pinfunction "2_2") (pintype "passive"))
      (node (ref "OPAMP6") (pin "6") (pinfunction "-_6") (pintype "passive"))
      (node (ref "OPAMP6") (pin "7") (pinfunction "OUT_7") (pintype "passive"))
    )
    (net (code "57") (name "Net-(OPAMP6C-+)") (class "Default")
      (node (ref "C61") (pin "2") (pinfunction "2_2") (pintype "passive"))
      (node (ref "OPAMP6") (pin "10") (pinfunction "+_10") (pintype "passive"))
      (node (ref "R61") (pin "2") (pinfunction "2_2") (pintype "passive"))
    )
    (net (code "58") (name "Net-(OPAMP6C--)") (class "Default")
      (node (ref "C62") (pin "2") (pinfunction "2_2") (pintype "passive"))
      (node (ref "OPAMP6") (pin "8") (pinfunction "OUT_8") (pintype "passive"))
      (node (ref "OPAMP6") (pin "9") (pinfunction "-_9") (pintype "passive"))
    )
    (net (code "59") (name "Net-(OPAMP6D-+)") (class "Default")
      (node (ref "OPAMP6") (pin "12") (pinfunction "+_12") (pintype "passive"))
      (node (ref "R55") (pin "2") (pinfunction "2_2") (pintype "passive"))
      (node (ref "R58") (pin "2") (pinfunction "2_2") (pintype "passive"))
      (node (ref "R59") (pin "2") (pinfunction "2_2") (pintype "passive"))
      (node (ref "R60") (pin "1") (pinfunction "1_1") (pintype "passive"))
    )
    (net (code "60") (name "Net-(OPAMP6D--)") (class "Default")
      (node (ref "C63") (pin "1") (pinfunction "1_1") (pintype "passive"))
      (node (ref "OPAMP6") (pin "13") (pinfunction "-_13") (pintype "passive"))
      (node (ref "R63") (pin "2") (pinfunction "2_2") (pintype "passive"))
      (node (ref "R64") (pin "1") (pinfunction "1_1") (pintype "passive"))
      (node (ref "R65") (pin "1") (pinfunction "1_1") (pintype "passive"))
      (node (ref "TP22") (pin "1") (pinfunction "TP_1") (pintype "passive"))
    )
    (net (code "61") (name "Net-(Potentiometer2-2)") (class "Default")
      (node (ref "Potentiometer2") (pin "3") (pinfunction "2_3") (pintype "passive"))
      (node (ref "R77") (pin "2") (pinfunction "2_2") (pintype "passive"))
      (node (ref "R79") (pin "2") (pinfunction "2_2") (pintype "passive"))
    )
    (net (code "62") (name "Net-(Potentiometer2-Pad1)") (class "Default")
      (node (ref "Potentiometer2") (pin "1") (pinfunction "1_1") (pintype "passive"))
      (node (ref "R78") (pin "1") (pinfunction "1_1") (pintype "passive"))
    )
  )
)
